# led_pack21.net
KiCad netlist of a schematic drawn in Altium Designer
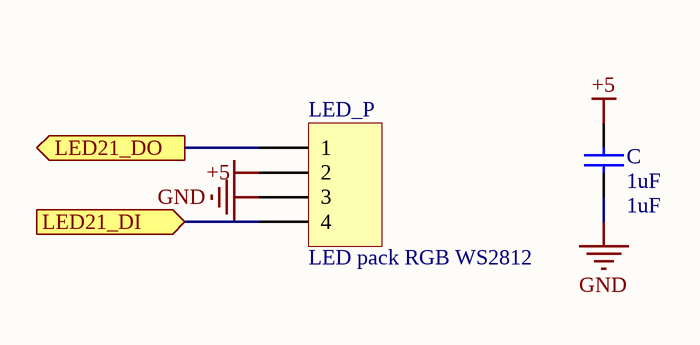
[diagram p0: led_pack21.SchDoc]

(export (version "E")
  (design (tool "Eeschema 10.0.6"))
  (components
    (comp (ref "C")
      (value "1uF")
      (footprint "0603C")
      (description "CAP SMD 0603")
      (fields (field (name "ALTIUM_VALUE") "1uF") (field (name "PUBLISHER") "Altium Limited"))
      (libsource (lib "Miscellaneous Devices") (part "Cap"))
    )
    (comp (ref "LED_P")
      (value "LED pack RGB WS2812")
      (footprint "pack21-2121")
      (description "5 RGB LED pack")
      (fields (field (name "PUBLISHER") "Altium Limited"))
      (libsource (lib "Altium") (part "Header 4"))
    )
  )
  (nets
    (net (code "1") (name "+5") (class "Default")
      (node (ref "C") (pin "2") (pinfunction "2_2") (pintype "passive"))
      (node (ref "LED_P") (pin "2") (pinfunction "2_2") (pintype "passive"))
    )
    (net (code "2") (name "/LED21_DI") (class "Default")
      (node (ref "LED_P") (pin "4") (pinfunction "4_4") (pintype "passive"))
    )
    (net (code "3") (name "/LED21_DO") (class "Default")
      (node (ref "LED_P") (pin "1") (pinfunction "1_1") (pintype "passive"))
    )
    (net (code "4") (name "GND") (class "Default")
      (node (ref "C") (pin "1") (pinfunction "1_1") (pintype "passive"))
      (node (ref "LED_P") (pin "3") (pinfunction "3_3") (pintype "passive"))
    )
  )
)
